# ik_pikit_starter.net
KiCad netlist of a schematic drawn in EAGLE
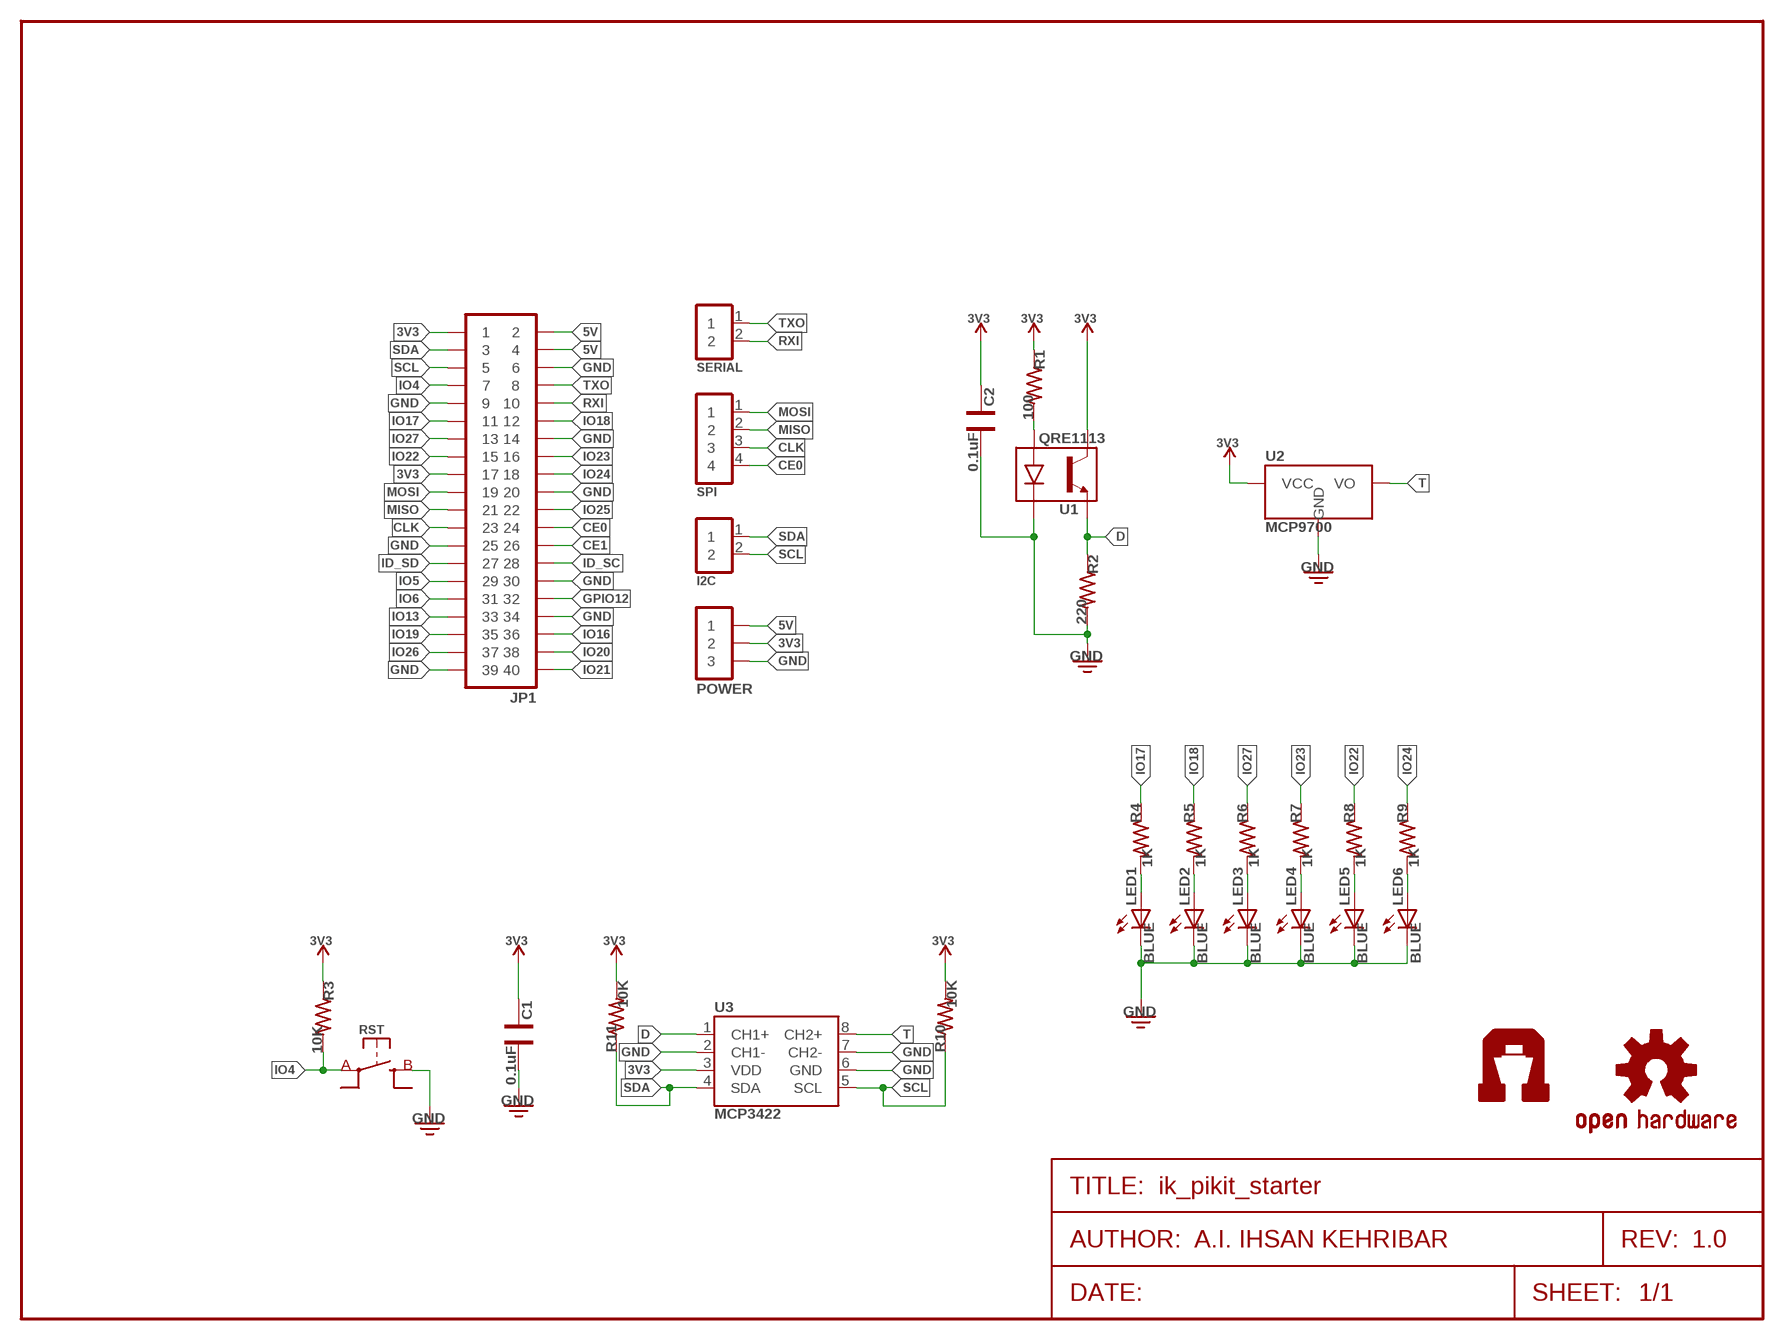
[diagram p0: schematic, sheet 1]

(export (version "E")
  (design (tool "Eeschema 10.0.6"))
  (components
    (comp (ref "C1")
      (value "0.1uF")
      (footprint "eagle-import:CAP-0805")
      (libsource (lib "eagle-import") (part "CAP0805"))
    )
    (comp (ref "C2")
      (value "0.1uF")
      (footprint "eagle-import:CAP-0805")
      (libsource (lib "eagle-import") (part "CAP0805"))
    )
    (comp (ref "I2C")
      (value "1X02NOFIRST")
      (footprint "eagle-import:1X02-NOFIRST")
      (libsource (lib "eagle-import") (part "1X02NOFIRST"))
    )
    (comp (ref "JP1")
      (value "2X20")
      (footprint "eagle-import:2X20-RPI-BRK")
      (libsource (lib "eagle-import") (part "2X20"))
    )
    (comp (ref "LED1")
      (value "BLUE")
      (footprint "eagle-import:LED-0805")
      (libsource (lib "eagle-import") (part "LED0805"))
    )
    (comp (ref "LED2")
      (value "BLUE")
      (footprint "eagle-import:LED-0805")
      (libsource (lib "eagle-import") (part "LED0805"))
    )
    (comp (ref "LED3")
      (value "BLUE")
      (footprint "eagle-import:LED-0805")
      (libsource (lib "eagle-import") (part "LED0805"))
    )
    (comp (ref "LED4")
      (value "BLUE")
      (footprint "eagle-import:LED-0805")
      (libsource (lib "eagle-import") (part "LED0805"))
    )
    (comp (ref "LED5")
      (value "BLUE")
      (footprint "eagle-import:LED-0805")
      (libsource (lib "eagle-import") (part "LED0805"))
    )
    (comp (ref "LED6")
      (value "BLUE")
      (footprint "eagle-import:LED-0805")
      (libsource (lib "eagle-import") (part "LED0805"))
    )
    (comp (ref "LOGO1")
      (value "OSHW-LOGOS")
      (footprint "eagle-import:OSHW-LOGO-S")
      (libsource (lib "eagle-import") (part "OSHW-LOGOS"))
    )
    (comp (ref "POWER")
      (value "1X03NOFIRST")
      (footprint "eagle-import:1X03-NOFIRST")
      (libsource (lib "eagle-import") (part "1X03NOFIRST"))
    )
    (comp (ref "R1")
      (value "100")
      (footprint "eagle-import:RES-0805")
      (libsource (lib "eagle-import") (part "RES0805"))
    )
    (comp (ref "R2")
      (value "220")
      (footprint "eagle-import:RES-0805")
      (libsource (lib "eagle-import") (part "RES0805"))
    )
    (comp (ref "R3")
      (value "10K")
      (footprint "eagle-import:RES-0805")
      (libsource (lib "eagle-import") (part "RES0805"))
    )
    (comp (ref "R4")
      (value "1K")
      (footprint "eagle-import:RES-0805")
      (libsource (lib "eagle-import") (part "RES0805"))
    )
    (comp (ref "R5")
      (value "1K")
      (footprint "eagle-import:RES-0805")
      (libsource (lib "eagle-import") (part "RES0805"))
    )
    (comp (ref "R6")
      (value "1K")
      (footprint "eagle-import:RES-0805")
      (libsource (lib "eagle-import") (part "RES0805"))
    )
    (comp (ref "R7")
      (value "1K")
      (footprint "eagle-import:RES-0805")
      (libsource (lib "eagle-import") (part "RES0805"))
    )
    (comp (ref "R8")
      (value "1K")
      (footprint "eagle-import:RES-0805")
      (libsource (lib "eagle-import") (part "RES0805"))
    )
    (comp (ref "R9")
      (value "1K")
      (footprint "eagle-import:RES-0805")
      (libsource (lib "eagle-import") (part "RES0805"))
    )
    (comp (ref "R10")
      (value "10K")
      (footprint "eagle-import:RES-0805")
      (libsource (lib "eagle-import") (part "RES0805"))
    )
    (comp (ref "R11")
      (value "10K")
      (footprint "eagle-import:RES-0805")
      (libsource (lib "eagle-import") (part "RES0805"))
    )
    (comp (ref "RST")
      (value "SW-SPSTSMD06X06")
      (footprint "eagle-import:SW-SPST-SMD06X06")
      (libsource (lib "eagle-import") (part "SW-SPSTSMD06X06"))
    )
    (comp (ref "SERIAL")
      (value "1X02NOFIRST")
      (footprint "eagle-import:1X02-NOFIRST")
      (libsource (lib "eagle-import") (part "1X02NOFIRST"))
    )
    (comp (ref "SPI")
      (value "1X04NOFIRST")
      (footprint "eagle-import:1X04-NOFIRST")
      (libsource (lib "eagle-import") (part "1X04NOFIRST"))
    )
    (comp (ref "U$3")
      (value "AI-LOGOXS")
      (footprint "eagle-import:AI-LOGO-XS")
      (libsource (lib "eagle-import") (part "AI-LOGOXS"))
    )
    (comp (ref "U1")
      (value "QRE1113")
      (footprint "eagle-import:QRE1113")
      (libsource (lib "eagle-import") (part "QRE1113"))
    )
    (comp (ref "U2")
      (value "MCP9700SMD")
      (footprint "eagle-import:SOT23-3")
      (libsource (lib "eagle-import") (part "MCP9700SMD"))
    )
    (comp (ref "U3")
      (value "MCP3422")
      (footprint "eagle-import:SO08")
      (libsource (lib "eagle-import") (part "MCP3422"))
    )
  )
  (nets
    (net (code "1") (name "3V3") (class "Default")
      (node (ref "C1") (pin "2") (pinfunction "2_2") (pintype "passive"))
      (node (ref "C2") (pin "2") (pinfunction "2_2") (pintype "passive"))
      (node (ref "JP1") (pin "1") (pinfunction "1_1") (pintype "bidirectional"))
      (node (ref "JP1") (pin "17") (pinfunction "17_17") (pintype "bidirectional"))
      (node (ref "POWER") (pin "2") (pinfunction "2_2") (pintype "bidirectional"))
      (node (ref "R1") (pin "1") (pinfunction "1_1") (pintype "passive"))
      (node (ref "R10") (pin "2") (pinfunction "2_2") (pintype "passive"))
      (node (ref "R11") (pin "2") (pinfunction "2_2") (pintype "passive"))
      (node (ref "R3") (pin "1") (pinfunction "1_1") (pintype "passive"))
      (node (ref "U1") (pin "3") (pinfunction "CO_3") (pintype "bidirectional"))
      (node (ref "U2") (pin "1") (pinfunction "VCC_1") (pintype "bidirectional"))
      (node (ref "U3") (pin "3") (pinfunction "VDD_3") (pintype "bidirectional"))
    )
    (net (code "2") (name "5V") (class "Default")
      (node (ref "JP1") (pin "2") (pinfunction "2_2") (pintype "bidirectional"))
      (node (ref "JP1") (pin "4") (pinfunction "4_4") (pintype "bidirectional"))
      (node (ref "POWER") (pin "1") (pinfunction "1_1") (pintype "bidirectional"))
    )
    (net (code "3") (name "CE0") (class "Default")
      (node (ref "JP1") (pin "24") (pinfunction "24_24") (pintype "bidirectional"))
      (node (ref "SPI") (pin "4") (pinfunction "4_4") (pintype "bidirectional"))
    )
    (net (code "4") (name "CE1") (class "Default")
      (node (ref "JP1") (pin "26") (pinfunction "26_26") (pintype "bidirectional"))
    )
    (net (code "5") (name "CLK") (class "Default")
      (node (ref "JP1") (pin "23") (pinfunction "23_23") (pintype "bidirectional"))
      (node (ref "SPI") (pin "3") (pinfunction "3_3") (pintype "bidirectional"))
    )
    (net (code "6") (name "D") (class "Default")
      (node (ref "R2") (pin "1") (pinfunction "1_1") (pintype "passive"))
      (node (ref "U1") (pin "4") (pinfunction "E_4") (pintype "bidirectional"))
      (node (ref "U3") (pin "1") (pinfunction "CH1+_1") (pintype "bidirectional"))
    )
    (net (code "7") (name "GND") (class "Default")
      (node (ref "C1") (pin "1") (pinfunction "1_1") (pintype "passive"))
      (node (ref "C2") (pin "1") (pinfunction "1_1") (pintype "passive"))
      (node (ref "JP1") (pin "14") (pinfunction "14_14") (pintype "bidirectional"))
      (node (ref "JP1") (pin "20") (pinfunction "20_20") (pintype "bidirectional"))
      (node (ref "JP1") (pin "25") (pinfunction "25_25") (pintype "bidirectional"))
      (node (ref "JP1") (pin "30") (pinfunction "30_30") (pintype "bidirectional"))
      (node (ref "JP1") (pin "34") (pinfunction "34_34") (pintype "bidirectional"))
      (node (ref "JP1") (pin "39") (pinfunction "39_39") (pintype "bidirectional"))
      (node (ref "JP1") (pin "6") (pinfunction "6_6") (pintype "bidirectional"))
      (node (ref "JP1") (pin "9") (pinfunction "9_9") (pintype "bidirectional"))
      (node (ref "LED1") (pin "C") (pinfunction "C_C") (pintype "passive"))
      (node (ref "LED2") (pin "C") (pinfunction "C_C") (pintype "passive"))
      (node (ref "LED3") (pin "C") (pinfunction "C_C") (pintype "passive"))
      (node (ref "LED4") (pin "C") (pinfunction "C_C") (pintype "passive"))
      (node (ref "LED5") (pin "C") (pinfunction "C_C") (pintype "passive"))
      (node (ref "LED6") (pin "C") (pinfunction "C_C") (pintype "passive"))
      (node (ref "POWER") (pin "3") (pinfunction "3_3") (pintype "bidirectional"))
      (node (ref "R2") (pin "2") (pinfunction "2_2") (pintype "passive"))
      (node (ref "RST") (pin "B@1") (pinfunction "B_B@1") (pintype "passive"))
      (node (ref "RST") (pin "B@2") (pinfunction "B_B@2") (pintype "passive"))
      (node (ref "U1") (pin "2") (pinfunction "CA_2") (pintype "bidirectional"))
      (node (ref "U2") (pin "3") (pinfunction "GND_3") (pintype "bidirectional"))
      (node (ref "U3") (pin "2") (pinfunction "CH1-_2") (pintype "bidirectional"))
      (node (ref "U3") (pin "6") (pinfunction "GND_6") (pintype "bidirectional"))
      (node (ref "U3") (pin "7") (pinfunction "CH2-_7") (pintype "bidirectional"))
    )
    (net (code "8") (name "GPIO12") (class "Default")
      (node (ref "JP1") (pin "32") (pinfunction "32_32") (pintype "bidirectional"))
    )
    (net (code "9") (name "ID_SC") (class "Default")
      (node (ref "JP1") (pin "28") (pinfunction "28_28") (pintype "bidirectional"))
    )
    (net (code "10") (name "ID_SD") (class "Default")
      (node (ref "JP1") (pin "27") (pinfunction "27_27") (pintype "bidirectional"))
    )
    (net (code "11") (name "IO4") (class "Default")
      (node (ref "JP1") (pin "7") (pinfunction "7_7") (pintype "bidirectional"))
      (node (ref "R3") (pin "2") (pinfunction "2_2") (pintype "passive"))
      (node (ref "RST") (pin "A@1") (pinfunction "A_A@1") (pintype "passive"))
      (node (ref "RST") (pin "A@2") (pinfunction "A_A@2") (pintype "passive"))
    )
    (net (code "12") (name "IO5") (class "Default")
      (node (ref "JP1") (pin "29") (pinfunction "29_29") (pintype "bidirectional"))
    )
    (net (code "13") (name "IO6") (class "Default")
      (node (ref "JP1") (pin "31") (pinfunction "31_31") (pintype "bidirectional"))
    )
    (net (code "14") (name "IO13") (class "Default")
      (node (ref "JP1") (pin "33") (pinfunction "33_33") (pintype "bidirectional"))
    )
    (net (code "15") (name "IO16") (class "Default")
      (node (ref "JP1") (pin "36") (pinfunction "36_36") (pintype "bidirectional"))
    )
    (net (code "16") (name "IO17") (class "Default")
      (node (ref "JP1") (pin "11") (pinfunction "11_11") (pintype "bidirectional"))
      (node (ref "R4") (pin "1") (pinfunction "1_1") (pintype "passive"))
    )
    (net (code "17") (name "IO18") (class "Default")
      (node (ref "JP1") (pin "12") (pinfunction "12_12") (pintype "bidirectional"))
      (node (ref "R5") (pin "1") (pinfunction "1_1") (pintype "passive"))
    )
    (net (code "18") (name "IO19") (class "Default")
      (node (ref "JP1") (pin "35") (pinfunction "35_35") (pintype "bidirectional"))
    )
    (net (code "19") (name "IO20") (class "Default")
      (node (ref "JP1") (pin "38") (pinfunction "38_38") (pintype "bidirectional"))
    )
    (net (code "20") (name "IO21") (class "Default")
      (node (ref "JP1") (pin "40") (pinfunction "40_40") (pintype "bidirectional"))
    )
    (net (code "21") (name "IO22") (class "Default")
      (node (ref "JP1") (pin "15") (pinfunction "15_15") (pintype "bidirectional"))
      (node (ref "R8") (pin "1") (pinfunction "1_1") (pintype "passive"))
    )
    (net (code "22") (name "IO23") (class "Default")
      (node (ref "JP1") (pin "16") (pinfunction "16_16") (pintype "bidirectional"))
      (node (ref "R7") (pin "1") (pinfunction "1_1") (pintype "passive"))
    )
    (net (code "23") (name "IO24") (class "Default")
      (node (ref "JP1") (pin "18") (pinfunction "18_18") (pintype "bidirectional"))
      (node (ref "R9") (pin "1") (pinfunction "1_1") (pintype "passive"))
    )
    (net (code "24") (name "IO25") (class "Default")
      (node (ref "JP1") (pin "22") (pinfunction "22_22") (pintype "bidirectional"))
    )
    (net (code "25") (name "IO26") (class "Default")
      (node (ref "JP1") (pin "37") (pinfunction "37_37") (pintype "bidirectional"))
    )
    (net (code "26") (name "IO27") (class "Default")
      (node (ref "JP1") (pin "13") (pinfunction "13_13") (pintype "bidirectional"))
      (node (ref "R6") (pin "1") (pinfunction "1_1") (pintype "passive"))
    )
    (net (code "27") (name "MISO") (class "Default")
      (node (ref "JP1") (pin "21") (pinfunction "21_21") (pintype "bidirectional"))
      (node (ref "SPI") (pin "2") (pinfunction "2_2") (pintype "bidirectional"))
    )
    (net (code "28") (name "MOSI") (class "Default")
      (node (ref "JP1") (pin "19") (pinfunction "19_19") (pintype "bidirectional"))
      (node (ref "SPI") (pin "1") (pinfunction "1_1") (pintype "bidirectional"))
    )
    (net (code "29") (name "Net-(LED1-PadA)") (class "Default")
      (node (ref "LED1") (pin "A") (pinfunction "A_A") (pintype "passive"))
      (node (ref "R4") (pin "2") (pinfunction "2_2") (pintype "passive"))
    )
    (net (code "30") (name "Net-(LED2-PadA)") (class "Default")
      (node (ref "LED2") (pin "A") (pinfunction "A_A") (pintype "passive"))
      (node (ref "R5") (pin "2") (pinfunction "2_2") (pintype "passive"))
    )
    (net (code "31") (name "Net-(LED3-PadA)") (class "Default")
      (node (ref "LED3") (pin "A") (pinfunction "A_A") (pintype "passive"))
      (node (ref "R6") (pin "2") (pinfunction "2_2") (pintype "passive"))
    )
    (net (code "32") (name "Net-(LED4-PadA)") (class "Default")
      (node (ref "LED4") (pin "A") (pinfunction "A_A") (pintype "passive"))
      (node (ref "R7") (pin "2") (pinfunction "2_2") (pintype "passive"))
    )
    (net (code "33") (name "Net-(LED5-PadA)") (class "Default")
      (node (ref "LED5") (pin "A") (pinfunction "A_A") (pintype "passive"))
      (node (ref "R8") (pin "2") (pinfunction "2_2") (pintype "passive"))
    )
    (net (code "34") (name "Net-(LED6-PadA)") (class "Default")
      (node (ref "LED6") (pin "A") (pinfunction "A_A") (pintype "passive"))
      (node (ref "R9") (pin "2") (pinfunction "2_2") (pintype "passive"))
    )
    (net (code "35") (name "Net-(U1-A)") (class "Default")
      (node (ref "R1") (pin "2") (pinfunction "2_2") (pintype "passive"))
      (node (ref "U1") (pin "1") (pinfunction "A_1") (pintype "bidirectional"))
    )
    (net (code "36") (name "RXI") (class "Default")
      (node (ref "JP1") (pin "10") (pinfunction "10_10") (pintype "bidirectional"))
      (node (ref "SERIAL") (pin "2") (pinfunction "2_2") (pintype "bidirectional"))
    )
    (net (code "37") (name "SCL") (class "Default")
      (node (ref "I2C") (pin "2") (pinfunction "2_2") (pintype "bidirectional"))
      (node (ref "JP1") (pin "5") (pinfunction "5_5") (pintype "bidirectional"))
      (node (ref "R10") (pin "1") (pinfunction "1_1") (pintype "passive"))
      (node (ref "U3") (pin "5") (pinfunction "SCL_5") (pintype "bidirectional"))
    )
    (net (code "38") (name "SDA") (class "Default")
      (node (ref "I2C") (pin "1") (pinfunction "1_1") (pintype "bidirectional"))
      (node (ref "JP1") (pin "3") (pinfunction "3_3") (pintype "bidirectional"))
      (node (ref "R11") (pin "1") (pinfunction "1_1") (pintype "passive"))
      (node (ref "U3") (pin "4") (pinfunction "SDA_4") (pintype "bidirectional"))
    )
    (net (code "39") (name "T") (class "Default")
      (node (ref "U2") (pin "2") (pinfunction "VO_2") (pintype "bidirectional"))
      (node (ref "U3") (pin "8") (pinfunction "CH2+_8") (pintype "bidirectional"))
    )
    (net (code "40") (name "TXO") (class "Default")
      (node (ref "JP1") (pin "8") (pinfunction "8_8") (pintype "bidirectional"))
      (node (ref "SERIAL") (pin "1") (pinfunction "1_1") (pintype "bidirectional"))
    )
  )
)
